# FPGA.net
KiCad netlist of a schematic drawn in Altium Designer
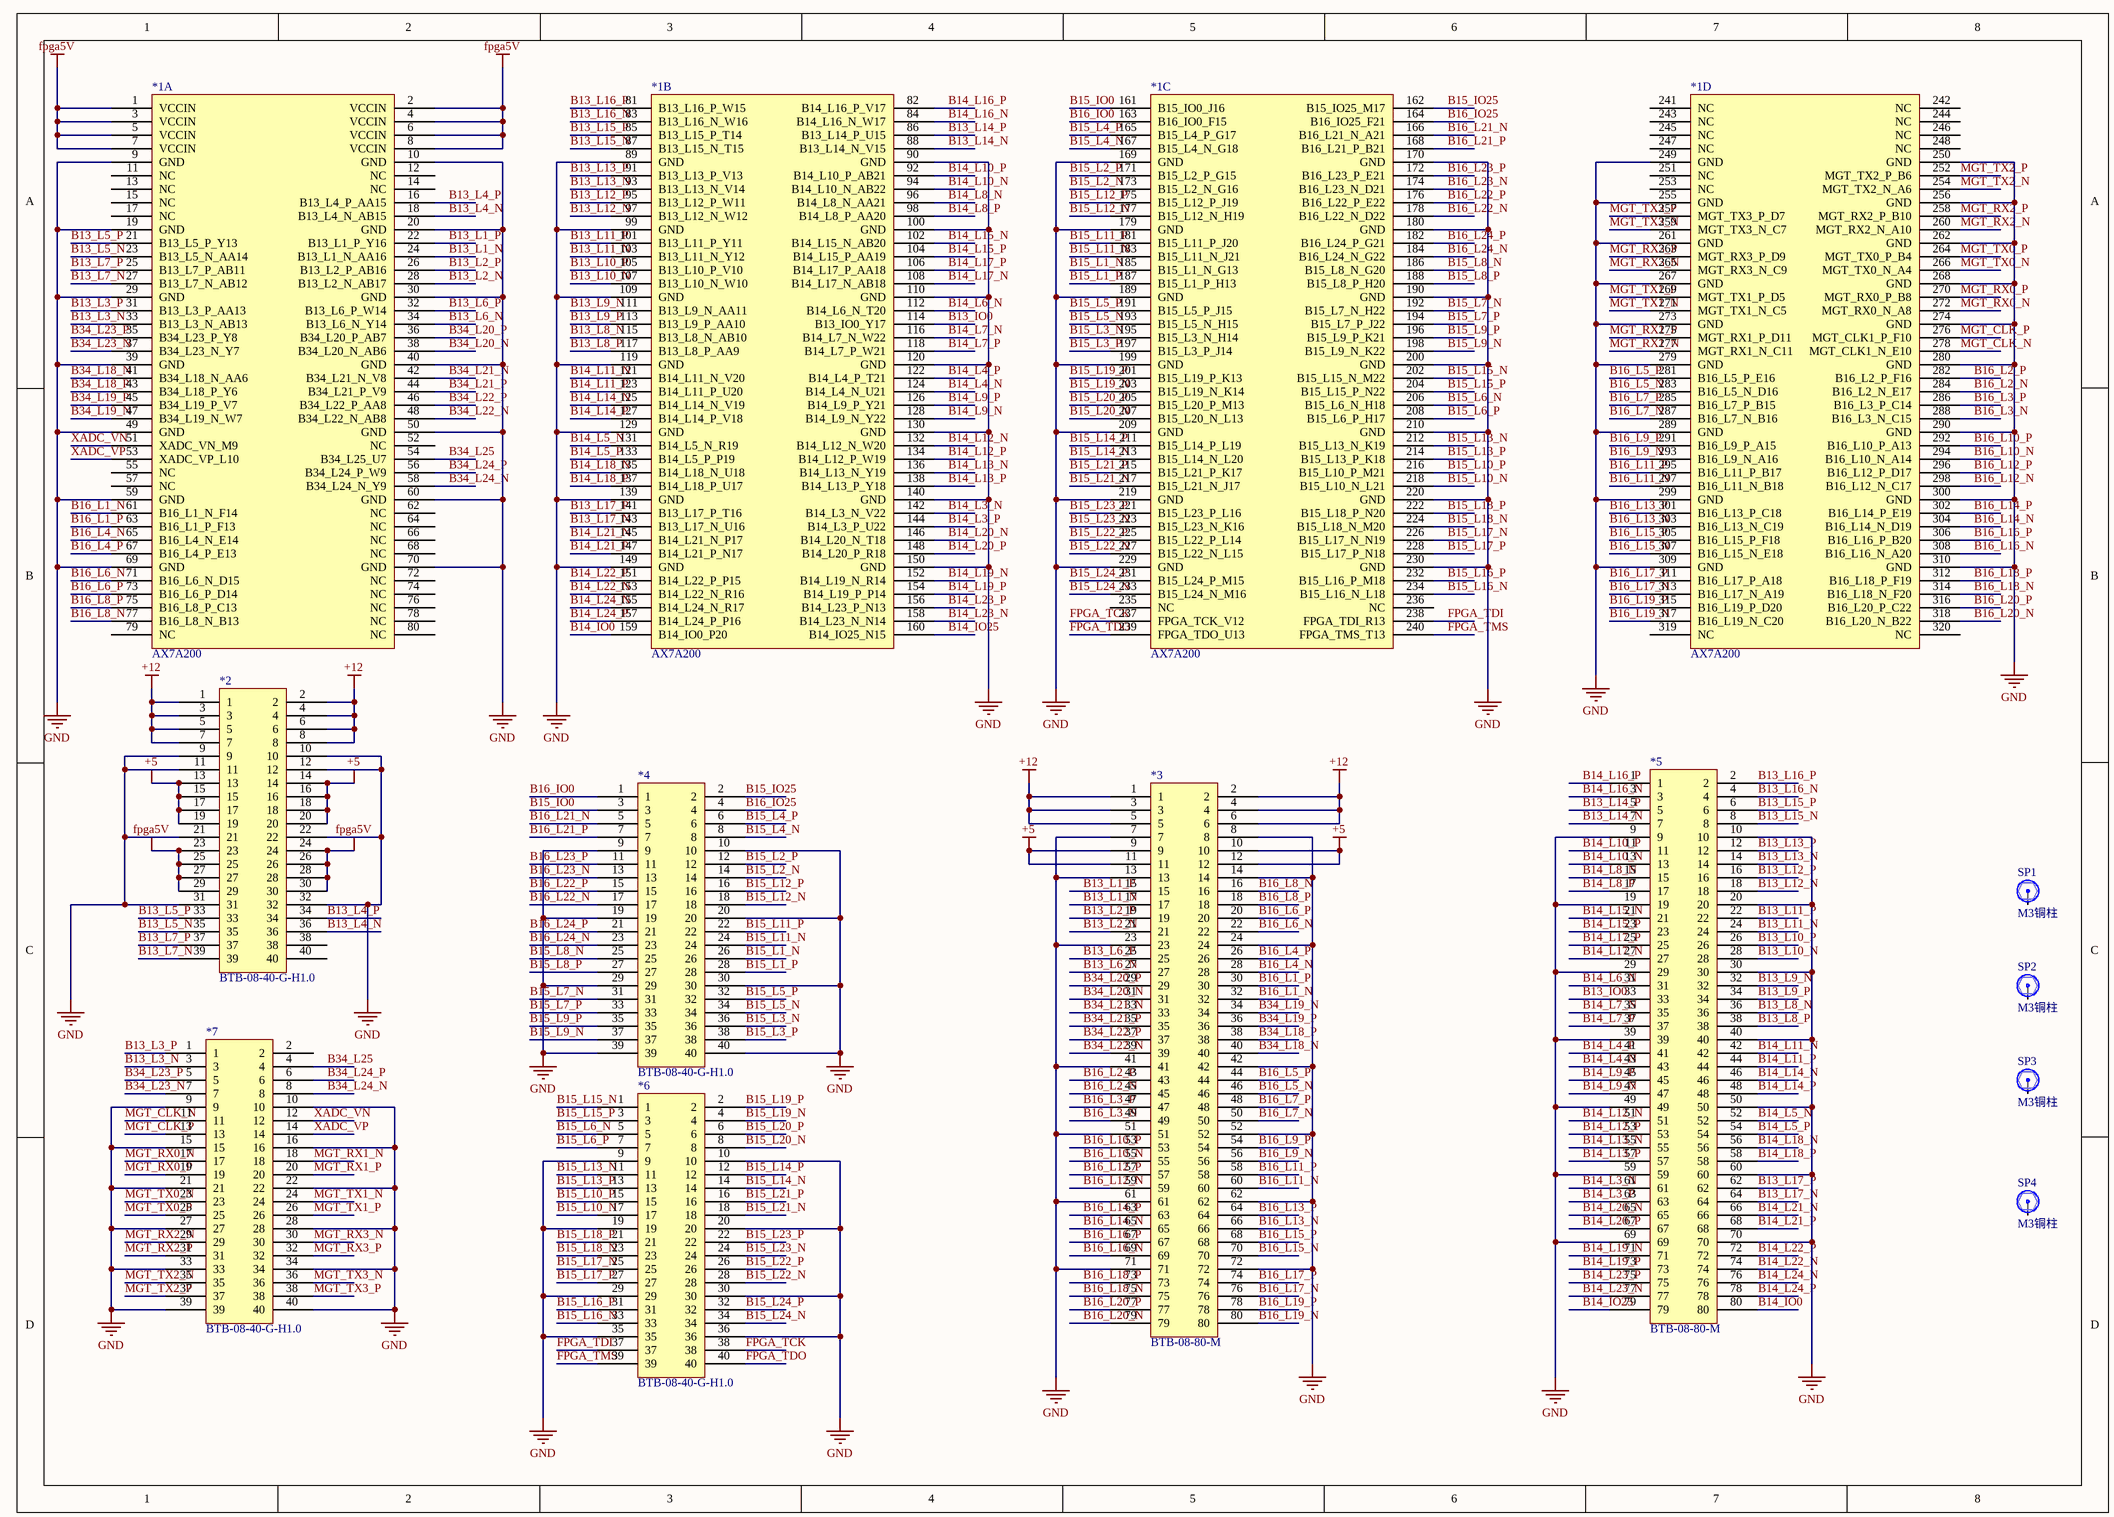
[diagram p0: FPGA.SchDoc]

(export (version "E")
  (design (tool "Eeschema 10.0.6"))
  (components
    (comp (ref "*1") (value "AX7A200") (footprint "AX7A200") (libsource (lib "0.02-模块") (part "AX7A200")))
    (comp (ref "*2")
      (value "BTB-08-40-G-H1.0")
      (footprint "BTB-08-40-G-H1.0")
      (libsource (lib "0.04连接器") (part "BTB-08-40-G-H1.0"))
    )
    (comp (ref "*3")
      (value "BTB-08-80-M")
      (footprint "BTB-08-80-M")
      (libsource (lib "0.04连接器") (part "BTB-08-80-G"))
    )
    (comp (ref "*4")
      (value "BTB-08-40-G-H1.0")
      (footprint "BTB-08-40-G-H1.0")
      (libsource (lib "0.04连接器") (part "BTB-08-40-G-H1.0"))
    )
    (comp (ref "*5")
      (value "BTB-08-80-M")
      (footprint "BTB-08-80-M")
      (libsource (lib "0.04连接器") (part "BTB-08-80-G"))
    )
    (comp (ref "*6")
      (value "BTB-08-40-G-H1.0")
      (footprint "BTB-08-40-G-H1.0")
      (libsource (lib "0.04连接器") (part "BTB-08-40-G-H1.0"))
    )
    (comp (ref "*7")
      (value "BTB-08-40-G-H1.0")
      (footprint "BTB-08-40-G-H1.0")
      (libsource (lib "0.04连接器") (part "BTB-08-40-G-H1.0"))
    )
    (comp (ref "SP1")
      (value "M3铜柱")
      (footprint "M3x10_N")
      (description "铜柱")
      (fields (field (name "版权归属") "封装库来自淘宝 ID：黄晶宝石"))
      (libsource (lib "9.09-固定柱") (part "铜柱大焊盘"))
    )
    (comp (ref "SP2")
      (value "M3铜柱")
      (footprint "M3x10_N")
      (description "铜柱")
      (fields (field (name "版权归属") "封装库来自淘宝 ID：黄晶宝石"))
      (libsource (lib "9.09-固定柱") (part "铜柱大焊盘"))
    )
    (comp (ref "SP3")
      (value "M3铜柱")
      (footprint "M3x10_N")
      (description "铜柱")
      (fields (field (name "版权归属") "封装库来自淘宝 ID：黄晶宝石"))
      (libsource (lib "9.09-固定柱") (part "铜柱大焊盘"))
    )
    (comp (ref "SP4")
      (value "M3铜柱")
      (footprint "M3x10_N")
      (description "铜柱")
      (fields (field (name "版权归属") "封装库来自淘宝 ID：黄晶宝石"))
      (libsource (lib "9.09-固定柱") (part "铜柱大焊盘"))
    )
  )
  (nets
    (net (code "1") (name "+5") (class "Default")
      (node (ref "*2") (pin "13") (pinfunction "13_13") (pintype "passive"))
      (node (ref "*2") (pin "14") (pinfunction "14_14") (pintype "passive"))
      (node (ref "*2") (pin "15") (pinfunction "15_15") (pintype "passive"))
      (node (ref "*2") (pin "16") (pinfunction "16_16") (pintype "passive"))
      (node (ref "*2") (pin "17") (pinfunction "17_17") (pintype "passive"))
      (node (ref "*2") (pin "18") (pinfunction "18_18") (pintype "passive"))
      (node (ref "*2") (pin "19") (pinfunction "19_19") (pintype "passive"))
      (node (ref "*2") (pin "20") (pinfunction "20_20") (pintype "passive"))
      (node (ref "*3") (pin "10") (pinfunction "10_10") (pintype "passive"))
      (node (ref "*3") (pin "11") (pinfunction "11_11") (pintype "passive"))
      (node (ref "*3") (pin "12") (pinfunction "12_12") (pintype "passive"))
      (node (ref "*3") (pin "9") (pinfunction "9_9") (pintype "passive"))
    )
    (net (code "2") (name "+12") (class "Default")
      (node (ref "*2") (pin "1") (pinfunction "1_1") (pintype "passive"))
      (node (ref "*2") (pin "2") (pinfunction "2_2") (pintype "passive"))
      (node (ref "*2") (pin "3") (pinfunction "3_3") (pintype "passive"))
      (node (ref "*2") (pin "4") (pinfunction "4_4") (pintype "passive"))
      (node (ref "*2") (pin "5") (pinfunction "5_5") (pintype "passive"))
      (node (ref "*2") (pin "6") (pinfunction "6_6") (pintype "passive"))
      (node (ref "*2") (pin "7") (pinfunction "7_7") (pintype "passive"))
      (node (ref "*2") (pin "8") (pinfunction "8_8") (pintype "passive"))
      (node (ref "*3") (pin "1") (pinfunction "1_1") (pintype "passive"))
      (node (ref "*3") (pin "2") (pinfunction "2_2") (pintype "passive"))
      (node (ref "*3") (pin "3") (pinfunction "3_3") (pintype "passive"))
      (node (ref "*3") (pin "4") (pinfunction "4_4") (pintype "passive"))
      (node (ref "*3") (pin "5") (pinfunction "5_5") (pintype "passive"))
      (node (ref "*3") (pin "6") (pinfunction "6_6") (pintype "passive"))
    )
    (net (code "3") (name "/B13_IO0") (class "Default")
      (node (ref "*1") (pin "114") (pinfunction "B13_IO0_Y17_114") (pintype "passive"))
      (node (ref "*5") (pin "33") (pinfunction "33_33") (pintype "passive"))
    )
    (net (code "4") (name "/B13_L1_N") (class "Default")
      (node (ref "*1") (pin "24") (pinfunction "B13_L1_N_AA16_24") (pintype "passive"))
      (node (ref "*3") (pin "17") (pinfunction "17_17") (pintype "passive"))
    )
    (net (code "5") (name "/B13_L1_P") (class "Default")
      (node (ref "*1") (pin "22") (pinfunction "B13_L1_P_Y16_22") (pintype "passive"))
      (node (ref "*3") (pin "15") (pinfunction "15_15") (pintype "passive"))
    )
    (net (code "6") (name "/B13_L2_N") (class "Default")
      (node (ref "*1") (pin "28") (pinfunction "B13_L2_N_AB17_28") (pintype "passive"))
      (node (ref "*3") (pin "21") (pinfunction "21_21") (pintype "passive"))
    )
    (net (code "7") (name "/B13_L2_P") (class "Default")
      (node (ref "*1") (pin "26") (pinfunction "B13_L2_P_AB16_26") (pintype "passive"))
      (node (ref "*3") (pin "19") (pinfunction "19_19") (pintype "passive"))
    )
    (net (code "8") (name "/B13_L3_N") (class "Default")
      (node (ref "*1") (pin "33") (pinfunction "B13_L3_N_AB13_33") (pintype "passive"))
      (node (ref "*7") (pin "3") (pinfunction "3_3") (pintype "passive"))
    )
    (net (code "9") (name "/B13_L3_P") (class "Default")
      (node (ref "*1") (pin "31") (pinfunction "B13_L3_P_AA13_31") (pintype "passive"))
      (node (ref "*7") (pin "1") (pinfunction "1_1") (pintype "passive"))
    )
    (net (code "10") (name "/B13_L4_N") (class "Default")
      (node (ref "*1") (pin "18") (pinfunction "B13_L4_N_AB15_18") (pintype "passive"))
      (node (ref "*2") (pin "36") (pinfunction "36_36") (pintype "passive"))
    )
    (net (code "11") (name "/B13_L4_P") (class "Default")
      (node (ref "*1") (pin "16") (pinfunction "B13_L4_P_AA15_16") (pintype "passive"))
      (node (ref "*2") (pin "34") (pinfunction "34_34") (pintype "passive"))
    )
    (net (code "12") (name "/B13_L5_N") (class "Default")
      (node (ref "*1") (pin "23") (pinfunction "B13_L5_N_AA14_23") (pintype "passive"))
      (node (ref "*2") (pin "35") (pinfunction "35_35") (pintype "passive"))
    )
    (net (code "13") (name "/B13_L5_P") (class "Default")
      (node (ref "*1") (pin "21") (pinfunction "B13_L5_P_Y13_21") (pintype "passive"))
      (node (ref "*2") (pin "33") (pinfunction "33_33") (pintype "passive"))
    )
    (net (code "14") (name "/B13_L6_N") (class "Default")
      (node (ref "*1") (pin "34") (pinfunction "B13_L6_N_Y14_34") (pintype "passive"))
      (node (ref "*3") (pin "27") (pinfunction "27_27") (pintype "passive"))
    )
    (net (code "15") (name "/B13_L6_P") (class "Default")
      (node (ref "*1") (pin "32") (pinfunction "B13_L6_P_W14_32") (pintype "passive"))
      (node (ref "*3") (pin "25") (pinfunction "25_25") (pintype "passive"))
    )
    (net (code "16") (name "/B13_L7_N") (class "Default")
      (node (ref "*1") (pin "27") (pinfunction "B13_L7_N_AB12_27") (pintype "passive"))
      (node (ref "*2") (pin "39") (pinfunction "39_39") (pintype "passive"))
    )
    (net (code "17") (name "/B13_L7_P") (class "Default")
      (node (ref "*1") (pin "25") (pinfunction "B13_L7_P_AB11_25") (pintype "passive"))
      (node (ref "*2") (pin "37") (pinfunction "37_37") (pintype "passive"))
    )
    (net (code "18") (name "/B13_L8_N") (class "Default")
      (node (ref "*1") (pin "115") (pinfunction "B13_L8_N_AB10_115") (pintype "passive"))
      (node (ref "*5") (pin "36") (pinfunction "36_36") (pintype "passive"))
    )
    (net (code "19") (name "/B13_L8_P") (class "Default")
      (node (ref "*1") (pin "117") (pinfunction "B13_L8_P_AA9_117") (pintype "passive"))
      (node (ref "*5") (pin "38") (pinfunction "38_38") (pintype "passive"))
    )
    (net (code "20") (name "/B13_L9_N") (class "Default")
      (node (ref "*1") (pin "111") (pinfunction "B13_L9_N_AA11_111") (pintype "passive"))
      (node (ref "*5") (pin "32") (pinfunction "32_32") (pintype "passive"))
    )
    (net (code "21") (name "/B13_L9_P") (class "Default")
      (node (ref "*1") (pin "113") (pinfunction "B13_L9_P_AA10_113") (pintype "passive"))
      (node (ref "*5") (pin "34") (pinfunction "34_34") (pintype "passive"))
    )
    (net (code "22") (name "/B13_L10_N") (class "Default")
      (node (ref "*1") (pin "107") (pinfunction "B13_L10_N_W10_107") (pintype "passive"))
      (node (ref "*5") (pin "28") (pinfunction "28_28") (pintype "passive"))
    )
    (net (code "23") (name "/B13_L10_P") (class "Default")
      (node (ref "*1") (pin "105") (pinfunction "B13_L10_P_V10_105") (pintype "passive"))
      (node (ref "*5") (pin "26") (pinfunction "26_26") (pintype "passive"))
    )
    (net (code "24") (name "/B13_L11_N") (class "Default")
      (node (ref "*1") (pin "103") (pinfunction "B13_L11_N_Y12_103") (pintype "passive"))
      (node (ref "*5") (pin "24") (pinfunction "24_24") (pintype "passive"))
    )
    (net (code "25") (name "/B13_L11_P") (class "Default")
      (node (ref "*1") (pin "101") (pinfunction "B13_L11_P_Y11_101") (pintype "passive"))
      (node (ref "*5") (pin "22") (pinfunction "22_22") (pintype "passive"))
    )
    (net (code "26") (name "/B13_L12_N") (class "Default")
      (node (ref "*1") (pin "97") (pinfunction "B13_L12_N_W12_97") (pintype "passive"))
      (node (ref "*5") (pin "18") (pinfunction "18_18") (pintype "passive"))
    )
    (net (code "27") (name "/B13_L12_P") (class "Default")
      (node (ref "*1") (pin "95") (pinfunction "B13_L12_P_W11_95") (pintype "passive"))
      (node (ref "*5") (pin "16") (pinfunction "16_16") (pintype "passive"))
    )
    (net (code "28") (name "/B13_L13_N") (class "Default")
      (node (ref "*1") (pin "93") (pinfunction "B13_L13_N_V14_93") (pintype "passive"))
      (node (ref "*5") (pin "14") (pinfunction "14_14") (pintype "passive"))
    )
    (net (code "29") (name "/B13_L13_P") (class "Default")
      (node (ref "*1") (pin "91") (pinfunction "B13_L13_P_V13_91") (pintype "passive"))
      (node (ref "*5") (pin "12") (pinfunction "12_12") (pintype "passive"))
    )
    (net (code "30") (name "/B13_L14_N") (class "Default")
      (node (ref "*1") (pin "88") (pinfunction "B13_L14_N_V15_88") (pintype "passive"))
      (node (ref "*5") (pin "7") (pinfunction "7_7") (pintype "passive"))
    )
    (net (code "31") (name "/B13_L14_P") (class "Default")
      (node (ref "*1") (pin "86") (pinfunction "B13_L14_P_U15_86") (pintype "passive"))
      (node (ref "*5") (pin "5") (pinfunction "5_5") (pintype "passive"))
    )
    (net (code "32") (name "/B13_L15_N") (class "Default")
      (node (ref "*1") (pin "87") (pinfunction "B13_L15_N_T15_87") (pintype "passive"))
      (node (ref "*5") (pin "8") (pinfunction "8_8") (pintype "passive"))
    )
    (net (code "33") (name "/B13_L15_P") (class "Default")
      (node (ref "*1") (pin "85") (pinfunction "B13_L15_P_T14_85") (pintype "passive"))
      (node (ref "*5") (pin "6") (pinfunction "6_6") (pintype "passive"))
    )
    (net (code "34") (name "/B13_L16_N") (class "Default")
      (node (ref "*1") (pin "83") (pinfunction "B13_L16_N_W16_83") (pintype "passive"))
      (node (ref "*5") (pin "4") (pinfunction "4_4") (pintype "passive"))
    )
    (net (code "35") (name "/B13_L16_P") (class "Default")
      (node (ref "*1") (pin "81") (pinfunction "B13_L16_P_W15_81") (pintype "passive"))
      (node (ref "*5") (pin "2") (pinfunction "2_2") (pintype "passive"))
    )
    (net (code "36") (name "/B13_L17_N") (class "Default")
      (node (ref "*1") (pin "143") (pinfunction "B13_L17_N_U16_143") (pintype "passive"))
      (node (ref "*5") (pin "64") (pinfunction "64_64") (pintype "passive"))
    )
    (net (code "37") (name "/B13_L17_P") (class "Default")
      (node (ref "*1") (pin "141") (pinfunction "B13_L17_P_T16_141") (pintype "passive"))
      (node (ref "*5") (pin "62") (pinfunction "62_62") (pintype "passive"))
    )
    (net (code "38") (name "/B14_IO0") (class "Default")
      (node (ref "*1") (pin "159") (pinfunction "B14_IO0_P20_159") (pintype "passive"))
      (node (ref "*5") (pin "80") (pinfunction "80_80") (pintype "passive"))
    )
    (net (code "39") (name "/B14_IO25") (class "Default")
      (node (ref "*1") (pin "160") (pinfunction "B14_IO25_N15_160") (pintype "passive"))
      (node (ref "*5") (pin "79") (pinfunction "79_79") (pintype "passive"))
    )
    (net (code "40") (name "/B14_L3_N") (class "Default")
      (node (ref "*1") (pin "142") (pinfunction "B14_L3_N_V22_142") (pintype "passive"))
      (node (ref "*5") (pin "61") (pinfunction "61_61") (pintype "passive"))
    )
    (net (code "41") (name "/B14_L3_P") (class "Default")
      (node (ref "*1") (pin "144") (pinfunction "B14_L3_P_U22_144") (pintype "passive"))
      (node (ref "*5") (pin "63") (pinfunction "63_63") (pintype "passive"))
    )
    (net (code "42") (name "/B14_L4_N") (class "Default")
      (node (ref "*1") (pin "124") (pinfunction "B14_L4_N_U21_124") (pintype "passive"))
      (node (ref "*5") (pin "43") (pinfunction "43_43") (pintype "passive"))
    )
    (net (code "43") (name "/B14_L4_P") (class "Default")
      (node (ref "*1") (pin "122") (pinfunction "B14_L4_P_T21_122") (pintype "passive"))
      (node (ref "*5") (pin "41") (pinfunction "41_41") (pintype "passive"))
    )
    (net (code "44") (name "/B14_L5_N") (class "Default")
      (node (ref "*1") (pin "131") (pinfunction "B14_L5_N_R19_131") (pintype "passive"))
      (node (ref "*5") (pin "52") (pinfunction "52_52") (pintype "passive"))
    )
    (net (code "45") (name "/B14_L5_P") (class "Default")
      (node (ref "*1") (pin "133") (pinfunction "B14_L5_P_P19_133") (pintype "passive"))
      (node (ref "*5") (pin "54") (pinfunction "54_54") (pintype "passive"))
    )
    (net (code "46") (name "/B14_L6_N") (class "Default")
      (node (ref "*1") (pin "112") (pinfunction "B14_L6_N_T20_112") (pintype "passive"))
      (node (ref "*5") (pin "31") (pinfunction "31_31") (pintype "passive"))
    )
    (net (code "47") (name "/B14_L7_N") (class "Default")
      (node (ref "*1") (pin "116") (pinfunction "B14_L7_N_W22_116") (pintype "passive"))
      (node (ref "*5") (pin "35") (pinfunction "35_35") (pintype "passive"))
    )
    (net (code "48") (name "/B14_L7_P") (class "Default")
      (node (ref "*1") (pin "118") (pinfunction "B14_L7_P_W21_118") (pintype "passive"))
      (node (ref "*5") (pin "37") (pinfunction "37_37") (pintype "passive"))
    )
    (net (code "49") (name "/B14_L8_N") (class "Default")
      (node (ref "*1") (pin "96") (pinfunction "B14_L8_N_AA21_96") (pintype "passive"))
      (node (ref "*5") (pin "15") (pinfunction "15_15") (pintype "passive"))
    )
    (net (code "50") (name "/B14_L8_P") (class "Default")
      (node (ref "*1") (pin "98") (pinfunction "B14_L8_P_AA20_98") (pintype "passive"))
      (node (ref "*5") (pin "17") (pinfunction "17_17") (pintype "passive"))
    )
    (net (code "51") (name "/B14_L9_N") (class "Default")
      (node (ref "*1") (pin "128") (pinfunction "B14_L9_N_Y22_128") (pintype "passive"))
      (node (ref "*5") (pin "47") (pinfunction "47_47") (pintype "passive"))
    )
    (net (code "52") (name "/B14_L9_P") (class "Default")
      (node (ref "*1") (pin "126") (pinfunction "B14_L9_P_Y21_126") (pintype "passive"))
      (node (ref "*5") (pin "45") (pinfunction "45_45") (pintype "passive"))
    )
    (net (code "53") (name "/B14_L10_N") (class "Default")
      (node (ref "*1") (pin "94") (pinfunction "B14_L10_N_AB22_94") (pintype "passive"))
      (node (ref "*5") (pin "13") (pinfunction "13_13") (pintype "passive"))
    )
    (net (code "54") (name "/B14_L10_P") (class "Default")
      (node (ref "*1") (pin "92") (pinfunction "B14_L10_P_AB21_92") (pintype "passive"))
      (node (ref "*5") (pin "11") (pinfunction "11_11") (pintype "passive"))
    )
    (net (code "55") (name "/B14_L11_N") (class "Default")
      (node (ref "*1") (pin "121") (pinfunction "B14_L11_N_V20_121") (pintype "passive"))
      (node (ref "*5") (pin "42") (pinfunction "42_42") (pintype "passive"))
    )
    (net (code "56") (name "/B14_L11_P") (class "Default")
      (node (ref "*1") (pin "123") (pinfunction "B14_L11_P_U20_123") (pintype "passive"))
      (node (ref "*5") (pin "44") (pinfunction "44_44") (pintype "passive"))
    )
    (net (code "57") (name "/B14_L12_N") (class "Default")
      (node (ref "*1") (pin "132") (pinfunction "B14_L12_N_W20_132") (pintype "passive"))
      (node (ref "*5") (pin "51") (pinfunction "51_51") (pintype "passive"))
    )
    (net (code "58") (name "/B14_L12_P") (class "Default")
      (node (ref "*1") (pin "134") (pinfunction "B14_L12_P_W19_134") (pintype "passive"))
      (node (ref "*5") (pin "53") (pinfunction "53_53") (pintype "passive"))
    )
    (net (code "59") (name "/B14_L13_N") (class "Default")
      (node (ref "*1") (pin "136") (pinfunction "B14_L13_N_Y19_136") (pintype "passive"))
      (node (ref "*5") (pin "55") (pinfunction "55_55") (pintype "passive"))
    )
    (net (code "60") (name "/B14_L13_P") (class "Default")
      (node (ref "*1") (pin "138") (pinfunction "B14_L13_P_Y18_138") (pintype "passive"))
      (node (ref "*5") (pin "57") (pinfunction "57_57") (pintype "passive"))
    )
    (net (code "61") (name "/B14_L14_N") (class "Default")
      (node (ref "*1") (pin "125") (pinfunction "B14_L14_N_V19_125") (pintype "passive"))
      (node (ref "*5") (pin "46") (pinfunction "46_46") (pintype "passive"))
    )
    (net (code "62") (name "/B14_L14_P") (class "Default")
      (node (ref "*1") (pin "127") (pinfunction "B14_L14_P_V18_127") (pintype "passive"))
      (node (ref "*5") (pin "48") (pinfunction "48_48") (pintype "passive"))
    )
    (net (code "63") (name "/B14_L15_N") (class "Default")
      (node (ref "*1") (pin "102") (pinfunction "B14_L15_N_AB20_102") (pintype "passive"))
      (node (ref "*5") (pin "21") (pinfunction "21_21") (pintype "passive"))
    )
    (net (code "64") (name "/B14_L15_P") (class "Default")
      (node (ref "*1") (pin "104") (pinfunction "B14_L15_P_AA19_104") (pintype "passive"))
      (node (ref "*5") (pin "23") (pinfunction "23_23") (pintype "passive"))
    )
    (net (code "65") (name "/B14_L16_N") (class "Default")
      (node (ref "*1") (pin "84") (pinfunction "B14_L16_N_W17_84") (pintype "passive"))
      (node (ref "*5") (pin "3") (pinfunction "3_3") (pintype "passive"))
    )
    (net (code "66") (name "/B14_L16_P") (class "Default")
      (node (ref "*1") (pin "82") (pinfunction "B14_L16_P_V17_82") (pintype "passive"))
      (node (ref "*5") (pin "1") (pinfunction "1_1") (pintype "passive"))
    )
    (net (code "67") (name "/B14_L17_N") (class "Default")
      (node (ref "*1") (pin "108") (pinfunction "B14_L17_N_AB18_108") (pintype "passive"))
      (node (ref "*5") (pin "27") (pinfunction "27_27") (pintype "passive"))
    )
    (net (code "68") (name "/B14_L17_P") (class "Default")
      (node (ref "*1") (pin "106") (pinfunction "B14_L17_P_AA18_106") (pintype "passive"))
      (node (ref "*5") (pin "25") (pinfunction "25_25") (pintype "passive"))
    )
    (net (code "69") (name "/B14_L18_N") (class "Default")
      (node (ref "*1") (pin "135") (pinfunction "B14_L18_N_U18_135") (pintype "passive"))
      (node (ref "*5") (pin "56") (pinfunction "56_56") (pintype "passive"))
    )
    (net (code "70") (name "/B14_L18_P") (class "Default")
      (node (ref "*1") (pin "137") (pinfunction "B14_L18_P_U17_137") (pintype "passive"))
      (node (ref "*5") (pin "58") (pinfunction "58_58") (pintype "passive"))
    )
    (net (code "71") (name "/B14_L19_N") (class "Default")
      (node (ref "*1") (pin "152") (pinfunction "B14_L19_N_R14_152") (pintype "passive"))
      (node (ref "*5") (pin "71") (pinfunction "71_71") (pintype "passive"))
    )
    (net (code "72") (name "/B14_L19_P") (class "Default")
      (node (ref "*1") (pin "154") (pinfunction "B14_L19_P_P14_154") (pintype "passive"))
      (node (ref "*5") (pin "73") (pinfunction "73_73") (pintype "passive"))
    )
    (net (code "73") (name "/B14_L20_N") (class "Default")
      (node (ref "*1") (pin "146") (pinfunction "B14_L20_N_T18_146") (pintype "passive"))
      (node (ref "*5") (pin "65") (pinfunction "65_65") (pintype "passive"))
    )
    (net (code "74") (name "/B14_L20_P") (class "Default")
      (node (ref "*1") (pin "148") (pinfunction "B14_L20_P_R18_148") (pintype "passive"))
      (node (ref "*5") (pin "67") (pinfunction "67_67") (pintype "passive"))
    )
    (net (code "75") (name "/B14_L21_N") (class "Default")
      (node (ref "*1") (pin "145") (pinfunction "B14_L21_N_P17_145") (pintype "passive"))
      (node (ref "*5") (pin "66") (pinfunction "66_66") (pintype "passive"))
    )
    (net (code "76") (name "/B14_L21_P") (class "Default")
      (node (ref "*1") (pin "147") (pinfunction "B14_L21_P_N17_147") (pintype "passive"))
      (node (ref "*5") (pin "68") (pinfunction "68_68") (pintype "passive"))
    )
    (net (code "77") (name "/B14_L22_N") (class "Default")
      (node (ref "*1") (pin "153") (pinfunction "B14_L22_N_R16_153") (pintype "passive"))
      (node (ref "*5") (pin "74") (pinfunction "74_74") (pintype "passive"))
    )
    (net (code "78") (name "/B14_L22_P") (class "Default")
      (node (ref "*1") (pin "151") (pinfunction "B14_L22_P_P15_151") (pintype "passive"))
      (node (ref "*5") (pin "72") (pinfunction "72_72") (pintype "passive"))
    )
    (net (code "79") (name "/B14_L23_N") (class "Default")
      (node (ref "*1") (pin "158") (pinfunction "B14_L23_N_N14_158") (pintype "passive"))
      (node (ref "*5") (pin "77") (pinfunction "77_77") (pintype "passive"))
    )
    (net (code "80") (name "/B14_L23_P") (class "Default")
      (node (ref "*1") (pin "156") (pinfunction "B14_L23_P_N13_156") (pintype "passive"))
      (node (ref "*5") (pin "75") (pinfunction "75_75") (pintype "passive"))
    )
    (net (code "81") (name "/B14_L24_N") (class "Default")
      (node (ref "*1") (pin "155") (pinfunction "B14_L24_N_R17_155") (pintype "passive"))
      (node (ref "*5") (pin "76") (pinfunction "76_76") (pintype "passive"))
    )
    (net (code "82") (name "/B14_L24_P") (class "Default")
      (node (ref "*1") (pin "157") (pinfunction "B14_L24_P_P16_157") (pintype "passive"))
      (node (ref "*5") (pin "78") (pinfunction "78_78") (pintype "passive"))
    )
    (net (code "83") (name "/B15_IO0") (class "Default")
      (node (ref "*1") (pin "161") (pinfunction "B15_IO0_J16_161") (pintype "passive"))
      (node (ref "*4") (pin "3") (pinfunction "3_3") (pintype "passive"))
    )
    (net (code "84") (name "/B15_IO25") (class "Default")
      (node (ref "*1") (pin "162") (pinfunction "B15_IO25_M17_162") (pintype "passive"))
      (node (ref "*4") (pin "2") (pinfunction "2_2") (pintype "passive"))
    )
    (net (code "85") (name "/B15_L1_N") (class "Default")
      (node (ref "*1") (pin "185") (pinfunction "B15_L1_N_G13_185") (pintype "passive"))
      (node (ref "*4") (pin "26") (pinfunction "26_26") (pintype "passive"))
    )
    (net (code "86") (name "/B15_L1_P") (class "Default")
      (node (ref "*1") (pin "187") (pinfunction "B15_L1_P_H13_187") (pintype "passive"))
      (node (ref "*4") (pin "28") (pinfunction "28_28") (pintype "passive"))
    )
    (net (code "87") (name "/B15_L2_N") (class "Default")
      (node (ref "*1") (pin "173") (pinfunction "B15_L2_N_G16_173") (pintype "passive"))
      (node (ref "*4") (pin "14") (pinfunction "14_14") (pintype "passive"))
    )
    (net (code "88") (name "/B15_L2_P") (class "Default")
      (node (ref "*1") (pin "171") (pinfunction "B15_L2_P_G15_171") (pintype "passive"))
      (node (ref "*4") (pin "12") (pinfunction "12_12") (pintype "passive"))
    )
    (net (code "89") (name "/B15_L3_N") (class "Default")
      (node (ref "*1") (pin "195") (pinfunction "B15_L3_N_H14_195") (pintype "passive"))
      (node (ref "*4") (pin "36") (pinfunction "36_36") (pintype "passive"))
    )
    (net (code "90") (name "/B15_L3_P") (class "Default")
      (node (ref "*1") (pin "197") (pinfunction "B15_L3_P_J14_197") (pintype "passive"))
      (node (ref "*4") (pin "38") (pinfunction "38_38") (pintype "passive"))
    )
    (net (code "91") (name "/B15_L4_N") (class "Default")
      (node (ref "*1") (pin "167") (pinfunction "B15_L4_N_G18_167") (pintype "passive"))
      (node (ref "*4") (pin "8") (pinfunction "8_8") (pintype "passive"))
    )
    (net (code "92") (name "/B15_L4_P") (class "Default")
      (node (ref "*1") (pin "165") (pinfunction "B15_L4_P_G17_165") (pintype "passive"))
      (node (ref "*4") (pin "6") (pinfunction "6_6") (pintype "passive"))
    )
    (net (code "93") (name "/B15_L5_N") (class "Default")
      (node (ref "*1") (pin "193") (pinfunction "B15_L5_N_H15_193") (pintype "passive"))
      (node (ref "*4") (pin "34") (pinfunction "34_34") (pintype "passive"))
    )
    (net (code "94") (name "/B15_L5_P") (class "Default")
      (node (ref "*1") (pin "191") (pinfunction "B15_L5_P_J15_191") (pintype "passive"))
      (node (ref "*4") (pin "32") (pinfunction "32_32") (pintype "passive"))
    )
    (net (code "95") (name "/B15_L6_N") (class "Default")
      (node (ref "*1") (pin "206") (pinfunction "B15_L6_N_H18_206") (pintype "passive"))
      (node (ref "*6") (pin "5") (pinfunction "5_5") (pintype "passive"))
    )
    (net (code "96") (name "/B15_L6_P") (class "Default")
      (node (ref "*1") (pin "208") (pinfunction "B15_L6_P_H17_208") (pintype "passive"))
      (node (ref "*6") (pin "7") (pinfunction "7_7") (pintype "passive"))
    )
    (net (code "97") (name "/B15_L7_N") (class "Default")
      (node (ref "*1") (pin "192") (pinfunction "B15_L7_N_H22_192") (pintype "passive"))
      (node (ref "*4") (pin "31") (pinfunction "31_31") (pintype "passive"))
    )
    (net (code "98") (name "/B15_L7_P") (class "Default")
      (node (ref "*1") (pin "194") (pinfunction "B15_L7_P_J22_194") (pintype "passive"))
      (node (ref "*4") (pin "33") (pinfunction "33_33") (pintype "passive"))
    )
    (net (code "99") (name "/B15_L8_N") (class "Default")
      (node (ref "*1") (pin "186") (pinfunction "B15_L8_N_G20_186") (pintype "passive"))
      (node (ref "*4") (pin "25") (pinfunction "25_25") (pintype "passive"))
    )
    (net (code "100") (name "/B15_L8_P") (class "Default")
      (node (ref "*1") (pin "188") (pinfunction "B15_L8_P_H20_188") (pintype "passive"))
      (node (ref "*4") (pin "27") (pinfunction "27_27") (pintype "passive"))
    )
    (net (code "101") (name "/B15_L9_N") (class "Default")
      (node (ref "*1") (pin "198") (pinfunction "B15_L9_N_K22_198") (pintype "passive"))
      (node (ref "*4") (pin "37") (pinfunction "37_37") (pintype "passive"))
    )
    (net (code "102") (name "/B15_L9_P") (class "Default")
      (node (ref "*1") (pin "196") (pinfunction "B15_L9_P_K21_196") (pintype "passive"))
      (node (ref "*4") (pin "35") (pinfunction "35_35") (pintype "passive"))
    )
    (net (code "103") (name "/B15_L10_N") (class "Default")
      (node (ref "*1") (pin "218") (pinfunction "B15_L10_N_L21_218") (pintype "passive"))
      (node (ref "*6") (pin "17") (pinfunction "17_17") (pintype "passive"))
    )
    (net (code "104") (name "/B15_L10_P") (class "Default")
      (node (ref "*1") (pin "216") (pinfunction "B15_L10_P_M21_216") (pintype "passive"))
      (node (ref "*6") (pin "15") (pinfunction "15_15") (pintype "passive"))
    )
    (net (code "105") (name "/B15_L11_N") (class "Default")
      (node (ref "*1") (pin "183") (pinfunction "B15_L11_N_J21_183") (pintype "passive"))
      (node (ref "*4") (pin "24") (pinfunction "24_24") (pintype "passive"))
    )
    (net (code "106") (name "/B15_L11_P") (class "Default")
      (node (ref "*1") (pin "181") (pinfunction "B15_L11_P_J20_181") (pintype "passive"))
      (node (ref "*4") (pin "22") (pinfunction "22_22") (pintype "passive"))
    )
    (net (code "107") (name "/B15_L12_N") (class "Default")
      (node (ref "*1") (pin "177") (pinfunction "B15_L12_N_H19_177") (pintype "passive"))
      (node (ref "*4") (pin "18") (pinfunction "18_18") (pintype "passive"))
    )
    (net (code "108") (name "/B15_L12_P") (class "Default")
      (node (ref "*1") (pin "175") (pinfunction "B15_L12_P_J19_175") (pintype "passive"))
      (node (ref "*4") (pin "16") (pinfunction "16_16") (pintype "passive"))
    )
    (net (code "109") (name "/B15_L13_N") (class "Default")
      (node (ref "*1") (pin "212") (pinfunction "B15_L13_N_K19_212") (pintype "passive"))
      (node (ref "*6") (pin "11") (pinfunction "11_11") (pintype "passive"))
    )
    (net (code "110") (name "/B15_L13_P") (class "Default")
      (node (ref "*1") (pin "214") (pinfunction "B15_L13_P_K18_214") (pintype "passive"))
      (node (ref "*6") (pin "13") (pinfunction "13_13") (pintype "passive"))
    )
    (net (code "111") (name "/B15_L14_N") (class "Default")
      (node (ref "*1") (pin "213") (pinfunction "B15_L14_N_L20_213") (pintype "passive"))
      (node (ref "*6") (pin "14") (pinfunction "14_14") (pintype "passive"))
    )
    (net (code "112") (name "/B15_L14_P") (class "Default")
      (node (ref "*1") (pin "211") (pinfunction "B15_L14_P_L19_211") (pintype "passive"))
      (node (ref "*6") (pin "12") (pinfunction "12_12") (pintype "passive"))
    )
    (net (code "113") (name "/B15_L15_N") (class "Default")
      (node (ref "*1") (pin "202") (pinfunction "B15_L15_N_M22_202") (pintype "passive"))
      (node (ref "*6") (pin "1") (pinfunction "1_1") (pintype "passive"))
    )
    (net (code "114") (name "/B15_L15_P") (class "Default")
      (node (ref "*1") (pin "204") (pinfunction "B15_L15_P_N22_204") (pintype "passive"))
      (node (ref "*6") (pin "3") (pinfunction "3_3") (pintype "passive"))
    )
    (net (code "115") (name "/B15_L16_N") (class "Default")
      (node (ref "*1") (pin "234") (pinfunction "B15_L16_N_L18_234") (pintype "passive"))
      (node (ref "*6") (pin "33") (pinfunction "33_33") (pintype "passive"))
    )
    (net (code "116") (name "/B15_L16_P") (class "Default")
      (node (ref "*1") (pin "232") (pinfunction "B15_L16_P_M18_232") (pintype "passive"))
      (node (ref "*6") (pin "31") (pinfunction "31_31") (pintype "passive"))
    )
    (net (code "117") (name "/B15_L17_N") (class "Default")
      (node (ref "*1") (pin "226") (pinfunction "B15_L17_N_N19_226") (pintype "passive"))
      (node (ref "*6") (pin "25") (pinfunction "25_25") (pintype "passive"))
    )
    (net (code "118") (name "/B15_L17_P") (class "Default")
      (node (ref "*1") (pin "228") (pinfunction "B15_L17_P_N18_228") (pintype "passive"))
      (node (ref "*6") (pin "27") (pinfunction "27_27") (pintype "passive"))
    )
    (net (code "119") (name "/B15_L18_N") (class "Default")
      (node (ref "*1") (pin "224") (pinfunction "B15_L18_N_M20_224") (pintype "passive"))
      (node (ref "*6") (pin "23") (pinfunction "23_23") (pintype "passive"))
    )
    (net (code "120") (name "/B15_L18_P") (class "Default")
      (node (ref "*1") (pin "222") (pinfunction "B15_L18_P_N20_222") (pintype "passive"))
      (node (ref "*6") (pin "21") (pinfunction "21_21") (pintype "passive"))
    )
    (net (code "121") (name "/B15_L19_N") (class "Default")
      (node (ref "*1") (pin "203") (pinfunction "B15_L19_N_K14_203") (pintype "passive"))
      (node (ref "*6") (pin "4") (pinfunction "4_4") (pintype "passive"))
    )
    (net (code "122") (name "/B15_L19_P") (class "Default")
      (node (ref "*1") (pin "201") (pinfunction "B15_L19_P_K13_201") (pintype "passive"))
      (node (ref "*6") (pin "2") (pinfunction "2_2") (pintype "passive"))
    )
    (net (code "123") (name "/B15_L20_N") (class "Default")
      (node (ref "*1") (pin "207") (pinfunction "B15_L20_N_L13_207") (pintype "passive"))
      (node (ref "*6") (pin "8") (pinfunction "8_8") (pintype "passive"))
    )
    (net (code "124") (name "/B15_L20_P") (class "Default")
      (node (ref "*1") (pin "205") (pinfunction "B15_L20_P_M13_205") (pintype "passive"))
      (node (ref "*6") (pin "6") (pinfunction "6_6") (pintype "passive"))
    )
    (net (code "125") (name "/B15_L21_N") (class "Default")
      (node (ref "*1") (pin "217") (pinfunction "B15_L21_N_J17_217") (pintype "passive"))
      (node (ref "*6") (pin "18") (pinfunction "18_18") (pintype "passive"))
    )
    (net (code "126") (name "/B15_L21_P") (class "Default")
      (node (ref "*1") (pin "215") (pinfunction "B15_L21_P_K17_215") (pintype "passive"))
      (node (ref "*6") (pin "16") (pinfunction "16_16") (pintype "passive"))
    )
    (net (code "127") (name "/B15_L22_N") (class "Default")
      (node (ref "*1") (pin "227") (pinfunction "B15_L22_N_L15_227") (pintype "passive"))
      (node (ref "*6") (pin "28") (pinfunction "28_28") (pintype "passive"))
    )
    (net (code "128") (name "/B15_L22_P") (class "Default")
      (node (ref "*1") (pin "225") (pinfunction "B15_L22_P_L14_225") (pintype "passive"))
      (node (ref "*6") (pin "26") (pinfunction "26_26") (pintype "passive"))
    )
    (net (code "129") (name "/B15_L23_N") (class "Default")
      (node (ref "*1") (pin "223") (pinfunction "B15_L23_N_K16_223") (pintype "passive"))
      (node (ref "*6") (pin "24") (pinfunction "24_24") (pintype "passive"))
    )
    (net (code "130") (name "/B15_L23_P") (class "Default")
      (node (ref "*1") (pin "221") (pinfunction "B15_L23_P_L16_221") (pintype "passive"))
      (node (ref "*6") (pin "22") (pinfunction "22_22") (pintype "passive"))
    )
    (net (code "131") (name "/B15_L24_N") (class "Default")
      (node (ref "*1") (pin "233") (pinfunction "B15_L24_N_M16_233") (pintype "passive"))
      (node (ref "*6") (pin "34") (pinfunction "34_34") (pintype "passive"))
    )
    (net (code "132") (name "/B15_L24_P") (class "Default")
      (node (ref "*1") (pin "231") (pinfunction "B15_L24_P_M15_231") (pintype "passive"))
      (node (ref "*6") (pin "32") (pinfunction "32_32") (pintype "passive"))
    )
    (net (code "133") (name "/B16_IO0") (class "Default")
      (node (ref "*1") (pin "163") (pinfunction "B16_IO0_F15_163") (pintype "passive"))
      (node (ref "*4") (pin "1") (pinfunction "1_1") (pintype "passive"))
    )
    (net (code "134") (name "/B16_IO25") (class "Default")
      (node (ref "*1") (pin "164") (pinfunction "B16_IO25_F21_164") (pintype "passive"))
      (node (ref "*4") (pin "4") (pinfunction "4_4") (pintype "passive"))
    )
    (net (code "135") (name "/B16_L1_N") (class "Default")
      (node (ref "*1") (pin "61") (pinfunction "B16_L1_N_F14_61") (pintype "passive"))
      (node (ref "*3") (pin "32") (pinfunction "32_32") (pintype "passive"))
    )
    (net (code "136") (name "/B16_L1_P") (class "Default")
      (node (ref "*1") (pin "63") (pinfunction "B16_L1_P_F13_63") (pintype "passive"))
      (node (ref "*3") (pin "30") (pinfunction "30_30") (pintype "passive"))
    )
    (net (code "137") (name "/B16_L2_N") (class "Default")
      (node (ref "*1") (pin "284") (pinfunction "B16_L2_N_E17_284") (pintype "passive"))
      (node (ref "*3") (pin "45") (pinfunction "45_45") (pintype "passive"))
    )
    (net (code "138") (name "/B16_L2_P") (class "Default")
      (node (ref "*1") (pin "282") (pinfunction "B16_L2_P_F16_282") (pintype "passive"))
      (node (ref "*3") (pin "43") (pinfunction "43_43") (pintype "passive"))
    )
    (net (code "139") (name "/B16_L3_N") (class "Default")
      (node (ref "*1") (pin "288") (pinfunction "B16_L3_N_C15_288") (pintype "passive"))
      (node (ref "*3") (pin "49") (pinfunction "49_49") (pintype "passive"))
    )
    (net (code "140") (name "/B16_L3_P") (class "Default")
      (node (ref "*1") (pin "286") (pinfunction "B16_L3_P_C14_286") (pintype "passive"))
      (node (ref "*3") (pin "47") (pinfunction "47_47") (pintype "passive"))
    )
    (net (code "141") (name "/B16_L4_N") (class "Default")
      (node (ref "*1") (pin "65") (pinfunction "B16_L4_N_E14_65") (pintype "passive"))
      (node (ref "*3") (pin "28") (pinfunction "28_28") (pintype "passive"))
    )
    (net (code "142") (name "/B16_L4_P") (class "Default")
      (node (ref "*1") (pin "67") (pinfunction "B16_L4_P_E13_67") (pintype "passive"))
      (node (ref "*3") (pin "26") (pinfunction "26_26") (pintype "passive"))
    )
    (net (code "143") (name "/B16_L5_N") (class "Default")
      (node (ref "*1") (pin "283") (pinfunction "B16_L5_N_D16_283") (pintype "passive"))
      (node (ref "*3") (pin "46") (pinfunction "46_46") (pintype "passive"))
    )
    (net (code "144") (name "/B16_L5_P") (class "Default")
      (node (ref "*1") (pin "281") (pinfunction "B16_L5_P_E16_281") (pintype "passive"))
      (node (ref "*3") (pin "44") (pinfunction "44_44") (pintype "passive"))
    )
    (net (code "145") (name "/B16_L6_N") (class "Default")
      (node (ref "*1") (pin "71") (pinfunction "B16_L6_N_D15_71") (pintype "passive"))
      (node (ref "*3") (pin "22") (pinfunction "22_22") (pintype "passive"))
    )
    (net (code "146") (name "/B16_L6_P") (class "Default")
      (node (ref "*1") (pin "73") (pinfunction "B16_L6_P_D14_73") (pintype "passive"))
      (node (ref "*3") (pin "20") (pinfunction "20_20") (pintype "passive"))
    )
    (net (code "147") (name "/B16_L7_N") (class "Default")
      (node (ref "*1") (pin "287") (pinfunction "B16_L7_N_B16_287") (pintype "passive"))
      (node (ref "*3") (pin "50") (pinfunction "50_50") (pintype "passive"))
    )
    (net (code "148") (name "/B16_L7_P") (class "Default")
      (node (ref "*1") (pin "285") (pinfunction "B16_L7_P_B15_285") (pintype "passive"))
      (node (ref "*3") (pin "48") (pinfunction "48_48") (pintype "passive"))
    )
    (net (code "149") (name "/B16_L8_N") (class "Default")
      (node (ref "*1") (pin "77") (pinfunction "B16_L8_N_B13_77") (pintype "passive"))
      (node (ref "*3") (pin "16") (pinfunction "16_16") (pintype "passive"))
    )
    (net (code "150") (name "/B16_L8_P") (class "Default")
      (node (ref "*1") (pin "75") (pinfunction "B16_L8_P_C13_75") (pintype "passive"))
      (node (ref "*3") (pin "18") (pinfunction "18_18") (pintype "passive"))
    )
    (net (code "151") (name "/B16_L9_N") (class "Default")
      (node (ref "*1") (pin "293") (pinfunction "B16_L9_N_A16_293") (pintype "passive"))
      (node (ref "*3") (pin "56") (pinfunction "56_56") (pintype "passive"))
    )
    (net (code "152") (name "/B16_L9_P") (class "Default")
      (node (ref "*1") (pin "291") (pinfunction "B16_L9_P_A15_291") (pintype "passive"))
      (node (ref "*3") (pin "54") (pinfunction "54_54") (pintype "passive"))
    )
    (net (code "153") (name "/B16_L10_N") (class "Default")
      (node (ref "*1") (pin "294") (pinfunction "B16_L10_N_A14_294") (pintype "passive"))
      (node (ref "*3") (pin "55") (pinfunction "55_55") (pintype "passive"))
    )
    (net (code "154") (name "/B16_L10_P") (class "Default")
      (node (ref "*1") (pin "292") (pinfunction "B16_L10_P_A13_292") (pintype "passive"))
      (node (ref "*3") (pin "53") (pinfunction "53_53") (pintype "passive"))
    )
    (net (code "155") (name "/B16_L11_N") (class "Default")
      (node (ref "*1") (pin "297") (pinfunction "B16_L11_N_B18_297") (pintype "passive"))
      (node (ref "*3") (pin "60") (pinfunction "60_60") (pintype "passive"))
    )
    (net (code "156") (name "/B16_L11_P") (class "Default")
      (node (ref "*1") (pin "295") (pinfunction "B16_L11_P_B17_295") (pintype "passive"))
      (node (ref "*3") (pin "58") (pinfunction "58_58") (pintype "passive"))
    )
    (net (code "157") (name "/B16_L12_N") (class "Default")
      (node (ref "*1") (pin "298") (pinfunction "B16_L12_N_C17_298") (pintype "passive"))
      (node (ref "*3") (pin "59") (pinfunction "59_59") (pintype "passive"))
    )
    (net (code "158") (name "/B16_L12_P") (class "Default")
      (node (ref "*1") (pin "296") (pinfunction "B16_L12_P_D17_296") (pintype "passive"))
      (node (ref "*3") (pin "57") (pinfunction "57_57") (pintype "passive"))
    )
    (net (code "159") (name "/B16_L13_N") (class "Default")
      (node (ref "*1") (pin "303") (pinfunction "B16_L13_N_C19_303") (pintype "passive"))
      (node (ref "*3") (pin "66") (pinfunction "66_66") (pintype "passive"))
    )
    (net (code "160") (name "/B16_L13_P") (class "Default")
      (node (ref "*1") (pin "301") (pinfunction "B16_L13_P_C18_301") (pintype "passive"))
      (node (ref "*3") (pin "64") (pinfunction "64_64") (pintype "passive"))
    )
    (net (code "161") (name "/B16_L14_N") (class "Default")
      (node (ref "*1") (pin "304") (pinfunction "B16_L14_N_D19_304") (pintype "passive"))
      (node (ref "*3") (pin "65") (pinfunction "65_65") (pintype "passive"))
    )
    (net (code "162") (name "/B16_L14_P") (class "Default")
      (node (ref "*1") (pin "302") (pinfunction "B16_L14_P_E19_302") (pintype "passive"))
      (node (ref "*3") (pin "63") (pinfunction "63_63") (pintype "passive"))
    )
    (net (code "163") (name "/B16_L15_N") (class "Default")
      (node (ref "*1") (pin "307") (pinfunction "B16_L15_N_E18_307") (pintype "passive"))
      (node (ref "*3") (pin "70") (pinfunction "70_70") (pintype "passive"))
    )
    (net (code "164") (name "/B16_L15_P") (class "Default")
      (node (ref "*1") (pin "305") (pinfunction "B16_L15_P_F18_305") (pintype "passive"))
      (node (ref "*3") (pin "68") (pinfunction "68_68") (pintype "passive"))
    )
    (net (code "165") (name "/B16_L16_N") (class "Default")
      (node (ref "*1") (pin "308") (pinfunction "B16_L16_N_A20_308") (pintype "passive"))
      (node (ref "*3") (pin "69") (pinfunction "69_69") (pintype "passive"))
    )
    (net (code "166") (name "/B16_L16_P") (class "Default")
      (node (ref "*1") (pin "306") (pinfunction "B16_L16_P_B20_306") (pintype "passive"))
      (node (ref "*3") (pin "67") (pinfunction "67_67") (pintype "passive"))
    )
    (net (code "167") (name "/B16_L17_N") (class "Default")
      (node (ref "*1") (pin "313") (pinfunction "B16_L17_N_A19_313") (pintype "passive"))
      (node (ref "*3") (pin "76") (pinfunction "76_76") (pintype "passive"))
    )
    (net (code "168") (name "/B16_L17_P") (class "Default")
      (node (ref "*1") (pin "311") (pinfunction "B16_L17_P_A18_311") (pintype "passive"))
      (node (ref "*3") (pin "74") (pinfunction "74_74") (pintype "passive"))
    )
    (net (code "169") (name "/B16_L18_N") (class "Default")
      (node (ref "*1") (pin "314") (pinfunction "B16_L18_N_F20_314") (pintype "passive"))
      (node (ref "*3") (pin "75") (pinfunction "75_75") (pintype "passive"))
    )
    (net (code "170") (name "/B16_L18_P") (class "Default")
      (node (ref "*1") (pin "312") (pinfunction "B16_L18_P_F19_312") (pintype "passive"))
      (node (ref "*3") (pin "73") (pinfunction "73_73") (pintype "passive"))
    )
    (net (code "171") (name "/B16_L19_N") (class "Default")
      (node (ref "*1") (pin "317") (pinfunction "B16_L19_N_C20_317") (pintype "passive"))
      (node (ref "*3") (pin "80") (pinfunction "80_80") (pintype "passive"))
    )
    (net (code "172") (name "/B16_L19_P") (class "Default")
      (node (ref "*1") (pin "315") (pinfunction "B16_L19_P_D20_315") (pintype "passive"))
      (node (ref "*3") (pin "78") (pinfunction "78_78") (pintype "passive"))
    )
    (net (code "173") (name "/B16_L20_N") (class "Default")
      (node (ref "*1") (pin "318") (pinfunction "B16_L20_N_B22_318") (pintype "passive"))
      (node (ref "*3") (pin "79") (pinfunction "79_79") (pintype "passive"))
    )
    (net (code "174") (name "/B16_L20_P") (class "Default")
      (node (ref "*1") (pin "316") (pinfunction "B16_L20_P_C22_316") (pintype "passive"))
      (node (ref "*3") (pin "77") (pinfunction "77_77") (pintype "passive"))
    )
    (net (code "175") (name "/B16_L21_N") (class "Default")
      (node (ref "*1") (pin "166") (pinfunction "B16_L21_N_A21_166") (pintype "passive"))
      (node (ref "*4") (pin "5") (pinfunction "5_5") (pintype "passive"))
    )
    (net (code "176") (name "/B16_L21_P") (class "Default")
      (node (ref "*1") (pin "168") (pinfunction "B16_L21_P_B21_168") (pintype "passive"))
      (node (ref "*4") (pin "7") (pinfunction "7_7") (pintype "passive"))
    )
    (net (code "177") (name "/B16_L22_N") (class "Default")
      (node (ref "*1") (pin "178") (pinfunction "B16_L22_N_D22_178") (pintype "passive"))
      (node (ref "*4") (pin "17") (pinfunction "17_17") (pintype "passive"))
    )
    (net (code "178") (name "/B16_L22_P") (class "Default")
      (node (ref "*1") (pin "176") (pinfunction "B16_L22_P_E22_176") (pintype "passive"))
      (node (ref "*4") (pin "15") (pinfunction "15_15") (pintype "passive"))
    )
    (net (code "179") (name "/B16_L23_N") (class "Default")
      (node (ref "*1") (pin "174") (pinfunction "B16_L23_N_D21_174") (pintype "passive"))
      (node (ref "*4") (pin "13") (pinfunction "13_13") (pintype "passive"))
    )
    (net (code "180") (name "/B16_L23_P") (class "Default")
      (node (ref "*1") (pin "172") (pinfunction "B16_L23_P_E21_172") (pintype "passive"))
      (node (ref "*4") (pin "11") (pinfunction "11_11") (pintype "passive"))
    )
    (net (code "181") (name "/B16_L24_N") (class "Default")
      (node (ref "*1") (pin "184") (pinfunction "B16_L24_N_G22_184") (pintype "passive"))
      (node (ref "*4") (pin "23") (pinfunction "23_23") (pintype "passive"))
    )
    (net (code "182") (name "/B16_L24_P") (class "Default")
      (node (ref "*1") (pin "182") (pinfunction "B16_L24_P_G21_182") (pintype "passive"))
      (node (ref "*4") (pin "21") (pinfunction "21_21") (pintype "passive"))
    )
    (net (code "183") (name "/B34_L18_N") (class "Default")
      (node (ref "*1") (pin "41") (pinfunction "B34_L18_N_AA6_41") (pintype "passive"))
      (node (ref "*3") (pin "40") (pinfunction "40_40") (pintype "passive"))
    )
    (net (code "184") (name "/B34_L18_P") (class "Default")
      (node (ref "*1") (pin "43") (pinfunction "B34_L18_P_Y6_43") (pintype "passive"))
      (node (ref "*3") (pin "38") (pinfunction "38_38") (pintype "passive"))
    )
    (net (code "185") (name "/B34_L19_N") (class "Default")
      (node (ref "*1") (pin "47") (pinfunction "B34_L19_N_W7_47") (pintype "passive"))
      (node (ref "*3") (pin "34") (pinfunction "34_34") (pintype "passive"))
    )
    (net (code "186") (name "/B34_L19_P") (class "Default")
      (node (ref "*1") (pin "45") (pinfunction "B34_L19_P_V7_45") (pintype "passive"))
      (node (ref "*3") (pin "36") (pinfunction "36_36") (pintype "passive"))
    )
    (net (code "187") (name "/B34_L20_N") (class "Default")
      (node (ref "*1") (pin "38") (pinfunction "B34_L20_N_AB6_38") (pintype "passive"))
      (node (ref "*3") (pin "31") (pinfunction "31_31") (pintype "passive"))
    )
    (net (code "188") (name "/B34_L20_P") (class "Default")
      (node (ref "*1") (pin "36") (pinfunction "B34_L20_P_AB7_36") (pintype "passive"))
      (node (ref "*3") (pin "29") (pinfunction "29_29") (pintype "passive"))
    )
    (net (code "189") (name "/B34_L21_N") (class "Default")
      (node (ref "*1") (pin "42") (pinfunction "B34_L21_N_V8_42") (pintype "passive"))
      (node (ref "*3") (pin "33") (pinfunction "33_33") (pintype "passive"))
    )
    (net (code "190") (name "/B34_L21_P") (class "Default")
      (node (ref "*1") (pin "44") (pinfunction "B34_L21_P_V9_44") (pintype "passive"))
      (node (ref "*3") (pin "35") (pinfunction "35_35") (pintype "passive"))
    )
    (net (code "191") (name "/B34_L22_N") (class "Default")
      (node (ref "*1") (pin "48") (pinfunction "B34_L22_N_AB8_48") (pintype "passive"))
      (node (ref "*3") (pin "39") (pinfunction "39_39") (pintype "passive"))
    )
    (net (code "192") (name "/B34_L22_P") (class "Default")
      (node (ref "*1") (pin "46") (pinfunction "B34_L22_P_AA8_46") (pintype "passive"))
      (node (ref "*3") (pin "37") (pinfunction "37_37") (pintype "passive"))
    )
    (net (code "193") (name "/B34_L23_N") (class "Default")
      (node (ref "*1") (pin "37") (pinfunction "B34_L23_N_Y7_37") (pintype "passive"))
      (node (ref "*7") (pin "7") (pinfunction "7_7") (pintype "passive"))
    )
    (net (code "194") (name "/B34_L23_P") (class "Default")
      (node (ref "*1") (pin "35") (pinfunction "B34_L23_P_Y8_35") (pintype "passive"))
      (node (ref "*7") (pin "5") (pinfunction "5_5") (pintype "passive"))
    )
    (net (code "195") (name "/B34_L24_N") (class "Default")
      (node (ref "*1") (pin "58") (pinfunction "B34_L24_N_Y9_58") (pintype "passive"))
      (node (ref "*7") (pin "8") (pinfunction "8_8") (pintype "passive"))
    )
    (net (code "196") (name "/B34_L24_P") (class "Default")
      (node (ref "*1") (pin "56") (pinfunction "B34_L24_P_W9_56") (pintype "passive"))
      (node (ref "*7") (pin "6") (pinfunction "6_6") (pintype "passive"))
    )
    (net (code "197") (name "/B34_L25") (class "Default")
      (node (ref "*1") (pin "54") (pinfunction "B34_L25_U7_54") (pintype "passive"))
      (node (ref "*7") (pin "4") (pinfunction "4_4") (pintype "passive"))
    )
    (net (code "198") (name "/FPGA_TCK") (class "Default")
      (node (ref "*1") (pin "237") (pinfunction "FPGA_TCK_V12_237") (pintype "passive"))
      (node (ref "*6") (pin "38") (pinfunction "38_38") (pintype "passive"))
    )
    (net (code "199") (name "/FPGA_TDI") (class "Default")
      (node (ref "*1") (pin "238") (pinfunction "FPGA_TDI_R13_238") (pintype "passive"))
      (node (ref "*6") (pin "37") (pinfunction "37_37") (pintype "passive"))
    )
    (net (code "200") (name "/FPGA_TDO") (class "Default")
      (node (ref "*1") (pin "239") (pinfunction "FPGA_TDO_U13_239") (pintype "passive"))
      (node (ref "*6") (pin "40") (pinfunction "40_40") (pintype "passive"))
    )
    (net (code "201") (name "/FPGA_TMS") (class "Default")
      (node (ref "*1") (pin "240") (pinfunction "FPGA_TMS_T13_240") (pintype "passive"))
      (node (ref "*6") (pin "39") (pinfunction "39_39") (pintype "passive"))
    )
    (net (code "202") (name "/MGT_CLK_N") (class "Default")
      (node (ref "*1") (pin "278") (pinfunction "MGT_CLK1_N_E10_278") (pintype "passive"))
      (node (ref "*7") (pin "11") (pinfunction "11_11") (pintype "passive"))
    )
    (net (code "203") (name "/MGT_CLK_P") (class "Default")
      (node (ref "*1") (pin "276") (pinfunction "MGT_CLK1_P_F10_276") (pintype "passive"))
      (node (ref "*7") (pin "13") (pinfunction "13_13") (pintype "passive"))
    )
    (net (code "204") (name "/MGT_RX0_N") (class "Default")
      (node (ref "*1") (pin "272") (pinfunction "MGT_RX0_N_A8_272") (pintype "passive"))
      (node (ref "*7") (pin "17") (pinfunction "17_17") (pintype "passive"))
    )
    (net (code "205") (name "/MGT_RX0_P") (class "Default")
      (node (ref "*1") (pin "270") (pinfunction "MGT_RX0_P_B8_270") (pintype "passive"))
      (node (ref "*7") (pin "19") (pinfunction "19_19") (pintype "passive"))
    )
    (net (code "206") (name "/MGT_RX1_N") (class "Default")
      (node (ref "*1") (pin "277") (pinfunction "MGT_RX1_N_C11_277") (pintype "passive"))
      (node (ref "*7") (pin "18") (pinfunction "18_18") (pintype "passive"))
    )
    (net (code "207") (name "/MGT_RX1_P") (class "Default")
      (node (ref "*1") (pin "275") (pinfunction "MGT_RX1_P_D11_275") (pintype "passive"))
      (node (ref "*7") (pin "20") (pinfunction "20_20") (pintype "passive"))
    )
    (net (code "208") (name "/MGT_RX2_N") (class "Default")
      (node (ref "*1") (pin "260") (pinfunction "MGT_RX2_N_A10_260") (pintype "passive"))
      (node (ref "*7") (pin "29") (pinfunction "29_29") (pintype "passive"))
    )
    (net (code "209") (name "/MGT_RX2_P") (class "Default")
      (node (ref "*1") (pin "258") (pinfunction "MGT_RX2_P_B10_258") (pintype "passive"))
      (node (ref "*7") (pin "31") (pinfunction "31_31") (pintype "passive"))
    )
    (net (code "210") (name "/MGT_RX3_N") (class "Default")
      (node (ref "*1") (pin "265") (pinfunction "MGT_RX3_N_C9_265") (pintype "passive"))
      (node (ref "*7") (pin "30") (pinfunction "30_30") (pintype "passive"))
    )
    (net (code "211") (name "/MGT_RX3_P") (class "Default")
      (node (ref "*1") (pin "263") (pinfunction "MGT_RX3_P_D9_263") (pintype "passive"))
      (node (ref "*7") (pin "32") (pinfunction "32_32") (pintype "passive"))
    )
    (net (code "212") (name "/MGT_TX0_N") (class "Default")
      (node (ref "*1") (pin "266") (pinfunction "MGT_TX0_N_A4_266") (pintype "passive"))
      (node (ref "*7") (pin "23") (pinfunction "23_23") (pintype "passive"))
    )
    (net (code "213") (name "/MGT_TX0_P") (class "Default")
      (node (ref "*1") (pin "264") (pinfunction "MGT_TX0_P_B4_264") (pintype "passive"))
      (node (ref "*7") (pin "25") (pinfunction "25_25") (pintype "passive"))
    )
    (net (code "214") (name "/MGT_TX1_N") (class "Default")
      (node (ref "*1") (pin "271") (pinfunction "MGT_TX1_N_C5_271") (pintype "passive"))
      (node (ref "*7") (pin "24") (pinfunction "24_24") (pintype "passive"))
    )
    (net (code "215") (name "/MGT_TX1_P") (class "Default")
      (node (ref "*1") (pin "269") (pinfunction "MGT_TX1_P_D5_269") (pintype "passive"))
      (node (ref "*7") (pin "26") (pinfunction "26_26") (pintype "passive"))
    )
    (net (code "216") (name "/MGT_TX2_N") (class "Default")
      (node (ref "*1") (pin "254") (pinfunction "MGT_TX2_N_A6_254") (pintype "passive"))
      (node (ref "*7") (pin "35") (pinfunction "35_35") (pintype "passive"))
    )
    (net (code "217") (name "/MGT_TX2_P") (class "Default")
      (node (ref "*1") (pin "252") (pinfunction "MGT_TX2_P_B6_252") (pintype "passive"))
      (node (ref "*7") (pin "37") (pinfunction "37_37") (pintype "passive"))
    )
    (net (code "218") (name "/MGT_TX3_N") (class "Default")
      (node (ref "*1") (pin "259") (pinfunction "MGT_TX3_N_C7_259") (pintype "passive"))
      (node (ref "*7") (pin "36") (pinfunction "36_36") (pintype "passive"))
    )
    (net (code "219") (name "/MGT_TX3_P") (class "Default")
      (node (ref "*1") (pin "257") (pinfunction "MGT_TX3_P_D7_257") (pintype "passive"))
      (node (ref "*7") (pin "38") (pinfunction "38_38") (pintype "passive"))
    )
    (net (code "220") (name "/XADC_VN") (class "Default")
      (node (ref "*1") (pin "51") (pinfunction "XADC_VN_M9_51") (pintype "passive"))
      (node (ref "*7") (pin "12") (pinfunction "12_12") (pintype "passive"))
    )
    (net (code "221") (name "/XADC_VP") (class "Default")
      (node (ref "*1") (pin "53") (pinfunction "XADC_VP_L10_53") (pintype "passive"))
      (node (ref "*7") (pin "14") (pinfunction "14_14") (pintype "passive"))
    )
    (net (code "222") (name "GND") (class "Default")
      (node (ref "*1") (pin "10") (pinfunction "GND_10") (pintype "passive"))
      (node (ref "*1") (pin "100") (pinfunction "GND_100") (pintype "passive"))
      (node (ref "*1") (pin "109") (pinfunction "GND_109") (pintype "passive"))
      (node (ref "*1") (pin "110") (pinfunction "GND_110") (pintype "passive"))
      (node (ref "*1") (pin "119") (pinfunction "GND_119") (pintype "passive"))
      (node (ref "*1") (pin "120") (pinfunction "GND_120") (pintype "passive"))
      (node (ref "*1") (pin "129") (pinfunction "GND_129") (pintype "passive"))
      (node (ref "*1") (pin "130") (pinfunction "GND_130") (pintype "passive"))
      (node (ref "*1") (pin "139") (pinfunction "GND_139") (pintype "passive"))
      (node (ref "*1") (pin "140") (pinfunction "GND_140") (pintype "passive"))
      (node (ref "*1") (pin "149") (pinfunction "GND_149") (pintype "passive"))
      (node (ref "*1") (pin "150") (pinfunction "GND_150") (pintype "passive"))
      (node (ref "*1") (pin "169") (pinfunction "GND_169") (pintype "passive"))
      (node (ref "*1") (pin "170") (pinfunction "GND_170") (pintype "passive"))
      (node (ref "*1") (pin "179") (pinfunction "GND_179") (pintype "passive"))
      (node (ref "*1") (pin "180") (pinfunction "GND_180") (pintype "passive"))
      (node (ref "*1") (pin "189") (pinfunction "GND_189") (pintype "passive"))
      (node (ref "*1") (pin "19") (pinfunction "GND_19") (pintype "passive"))
      (node (ref "*1") (pin "190") (pinfunction "GND_190") (pintype "passive"))
      (node (ref "*1") (pin "199") (pinfunction "GND_199") (pintype "passive"))
      (node (ref "*1") (pin "20") (pinfunction "GND_20") (pintype "passive"))
      (node (ref "*1") (pin "200") (pinfunction "GND_200") (pintype "passive"))
      (node (ref "*1") (pin "209") (pinfunction "GND_209") (pintype "passive"))
      (node (ref "*1") (pin "210") (pinfunction "GND_210") (pintype "passive"))
      (node (ref "*1") (pin "219") (pinfunction "GND_219") (pintype "passive"))
      (node (ref "*1") (pin "220") (pinfunction "GND_220") (pintype "passive"))
      (node (ref "*1") (pin "229") (pinfunction "GND_229") (pintype "passive"))
      (node (ref "*1") (pin "230") (pinfunction "GND_230") (pintype "passive"))
      (node (ref "*1") (pin "249") (pinfunction "GND_249") (pintype "passive"))
      (node (ref "*1") (pin "250") (pinfunction "GND_250") (pintype "passive"))
      (node (ref "*1") (pin "255") (pinfunction "GND_255") (pintype "passive"))
      (node (ref "*1") (pin "256") (pinfunction "GND_256") (pintype "passive"))
      (node (ref "*1") (pin "261") (pinfunction "GND_261") (pintype "passive"))
      (node (ref "*1") (pin "262") (pinfunction "GND_262") (pintype "passive"))
      (node (ref "*1") (pin "267") (pinfunction "GND_267") (pintype "passive"))
      (node (ref "*1") (pin "268") (pinfunction "GND_268") (pintype "passive"))
      (node (ref "*1") (pin "273") (pinfunction "GND_273") (pintype "passive"))
      (node (ref "*1") (pin "274") (pinfunction "GND_274") (pintype "passive"))
      (node (ref "*1") (pin "279") (pinfunction "GND_279") (pintype "passive"))
      (node (ref "*1") (pin "280") (pinfunction "GND_280") (pintype "passive"))
      (node (ref "*1") (pin "289") (pinfunction "GND_289") (pintype "passive"))
      (node (ref "*1") (pin "29") (pinfunction "GND_29") (pintype "passive"))
      (node (ref "*1") (pin "290") (pinfunction "GND_290") (pintype "passive"))
      (node (ref "*1") (pin "299") (pinfunction "GND_299") (pintype "passive"))
      (node (ref "*1") (pin "30") (pinfunction "GND_30") (pintype "passive"))
      (node (ref "*1") (pin "300") (pinfunction "GND_300") (pintype "passive"))
      (node (ref "*1") (pin "309") (pinfunction "GND_309") (pintype "passive"))
      (node (ref "*1") (pin "310") (pinfunction "GND_310") (pintype "passive"))
      (node (ref "*1") (pin "39") (pinfunction "GND_39") (pintype "passive"))
      (node (ref "*1") (pin "40") (pinfunction "GND_40") (pintype "passive"))
      (node (ref "*1") (pin "49") (pinfunction "GND_49") (pintype "passive"))
      (node (ref "*1") (pin "50") (pinfunction "GND_50") (pintype "passive"))
      (node (ref "*1") (pin "59") (pinfunction "GND_59") (pintype "passive"))
      (node (ref "*1") (pin "60") (pinfunction "GND_60") (pintype "passive"))
      (node (ref "*1") (pin "69") (pinfunction "GND_69") (pintype "passive"))
      (node (ref "*1") (pin "70") (pinfunction "GND_70") (pintype "passive"))
      (node (ref "*1") (pin "89") (pinfunction "GND_89") (pintype "passive"))
      (node (ref "*1") (pin "9") (pinfunction "GND_9") (pintype "passive"))
      (node (ref "*1") (pin "90") (pinfunction "GND_90") (pintype "passive"))
      (node (ref "*1") (pin "99") (pinfunction "GND_99") (pintype "passive"))
      (node (ref "*2") (pin "10") (pinfunction "10_10") (pintype "passive"))
      (node (ref "*2") (pin "11") (pinfunction "11_11") (pintype "passive"))
      (node (ref "*2") (pin "12") (pinfunction "12_12") (pintype "passive"))
      (node (ref "*2") (pin "21") (pinfunction "21_21") (pintype "passive"))
      (node (ref "*2") (pin "22") (pinfunction "22_22") (pintype "passive"))
      (node (ref "*2") (pin "31") (pinfunction "31_31") (pintype "passive"))
      (node (ref "*2") (pin "32") (pinfunction "32_32") (pintype "passive"))
      (node (ref "*2") (pin "9") (pinfunction "9_9") (pintype "passive"))
      (node (ref "*3") (pin "13") (pinfunction "13_13") (pintype "passive"))
      (node (ref "*3") (pin "14") (pinfunction "14_14") (pintype "passive"))
      (node (ref "*3") (pin "23") (pinfunction "23_23") (pintype "passive"))
      (node (ref "*3") (pin "24") (pinfunction "24_24") (pintype "passive"))
      (node (ref "*3") (pin "41") (pinfunction "41_41") (pintype "passive"))
      (node (ref "*3") (pin "42") (pinfunction "42_42") (pintype "passive"))
      (node (ref "*3") (pin "51") (pinfunction "51_51") (pintype "passive"))
      (node (ref "*3") (pin "52") (pinfunction "52_52") (pintype "passive"))
      (node (ref "*3") (pin "61") (pinfunction "61_61") (pintype "passive"))
      (node (ref "*3") (pin "62") (pinfunction "62_62") (pintype "passive"))
      (node (ref "*3") (pin "7") (pinfunction "7_7") (pintype "passive"))
      (node (ref "*3") (pin "71") (pinfunction "71_71") (pintype "passive"))
      (node (ref "*3") (pin "72") (pinfunction "72_72") (pintype "passive"))
      (node (ref "*3") (pin "8") (pinfunction "8_8") (pintype "passive"))
      (node (ref "*4") (pin "10") (pinfunction "10_10") (pintype "passive"))
      (node (ref "*4") (pin "19") (pinfunction "19_19") (pintype "passive"))
      (node (ref "*4") (pin "20") (pinfunction "20_20") (pintype "passive"))
      (node (ref "*4") (pin "29") (pinfunction "29_29") (pintype "passive"))
      (node (ref "*4") (pin "30") (pinfunction "30_30") (pintype "passive"))
      (node (ref "*4") (pin "39") (pinfunction "39_39") (pintype "passive"))
      (node (ref "*4") (pin "40") (pinfunction "40_40") (pintype "passive"))
      (node (ref "*4") (pin "9") (pinfunction "9_9") (pintype "passive"))
      (node (ref "*5") (pin "10") (pinfunction "10_10") (pintype "passive"))
      (node (ref "*5") (pin "19") (pinfunction "19_19") (pintype "passive"))
      (node (ref "*5") (pin "20") (pinfunction "20_20") (pintype "passive"))
      (node (ref "*5") (pin "29") (pinfunction "29_29") (pintype "passive"))
      (node (ref "*5") (pin "30") (pinfunction "30_30") (pintype "passive"))
      (node (ref "*5") (pin "39") (pinfunction "39_39") (pintype "passive"))
      (node (ref "*5") (pin "40") (pinfunction "40_40") (pintype "passive"))
      (node (ref "*5") (pin "49") (pinfunction "49_49") (pintype "passive"))
      (node (ref "*5") (pin "50") (pinfunction "50_50") (pintype "passive"))
      (node (ref "*5") (pin "59") (pinfunction "59_59") (pintype "passive"))
      (node (ref "*5") (pin "60") (pinfunction "60_60") (pintype "passive"))
      (node (ref "*5") (pin "69") (pinfunction "69_69") (pintype "passive"))
      (node (ref "*5") (pin "70") (pinfunction "70_70") (pintype "passive"))
      (node (ref "*5") (pin "9") (pinfunction "9_9") (pintype "passive"))
      (node (ref "*6") (pin "10") (pinfunction "10_10") (pintype "passive"))
      (node (ref "*6") (pin "19") (pinfunction "19_19") (pintype "passive"))
      (node (ref "*6") (pin "20") (pinfunction "20_20") (pintype "passive"))
      (node (ref "*6") (pin "29") (pinfunction "29_29") (pintype "passive"))
      (node (ref "*6") (pin "30") (pinfunction "30_30") (pintype "passive"))
      (node (ref "*6") (pin "35") (pinfunction "35_35") (pintype "passive"))
      (node (ref "*6") (pin "36") (pinfunction "36_36") (pintype "passive"))
      (node (ref "*6") (pin "9") (pinfunction "9_9") (pintype "passive"))
      (node (ref "*7") (pin "10") (pinfunction "10_10") (pintype "passive"))
      (node (ref "*7") (pin "15") (pinfunction "15_15") (pintype "passive"))
      (node (ref "*7") (pin "16") (pinfunction "16_16") (pintype "passive"))
      (node (ref "*7") (pin "21") (pinfunction "21_21") (pintype "passive"))
      (node (ref "*7") (pin "22") (pinfunction "22_22") (pintype "passive"))
      (node (ref "*7") (pin "27") (pinfunction "27_27") (pintype "passive"))
      (node (ref "*7") (pin "28") (pinfunction "28_28") (pintype "passive"))
      (node (ref "*7") (pin "33") (pinfunction "33_33") (pintype "passive"))
      (node (ref "*7") (pin "34") (pinfunction "34_34") (pintype "passive"))
      (node (ref "*7") (pin "39") (pinfunction "39_39") (pintype "passive"))
      (node (ref "*7") (pin "40") (pinfunction "40_40") (pintype "passive"))
      (node (ref "*7") (pin "9") (pinfunction "9_9") (pintype "passive"))
    )
    (net (code "223") (name "fpga5V") (class "Default")
      (node (ref "*1") (pin "1") (pinfunction "VCCIN_1") (pintype "passive"))
      (node (ref "*1") (pin "2") (pinfunction "VCCIN_2") (pintype "passive"))
      (node (ref "*1") (pin "3") (pinfunction "VCCIN_3") (pintype "passive"))
      (node (ref "*1") (pin "4") (pinfunction "VCCIN_4") (pintype "passive"))
      (node (ref "*1") (pin "5") (pinfunction "VCCIN_5") (pintype "passive"))
      (node (ref "*1") (pin "6") (pinfunction "VCCIN_6") (pintype "passive"))
      (node (ref "*1") (pin "7") (pinfunction "VCCIN_7") (pintype "passive"))
      (node (ref "*1") (pin "8") (pinfunction "VCCIN_8") (pintype "passive"))
      (node (ref "*2") (pin "23") (pinfunction "23_23") (pintype "passive"))
      (node (ref "*2") (pin "24") (pinfunction "24_24") (pintype "passive"))
      (node (ref "*2") (pin "25") (pinfunction "25_25") (pintype "passive"))
      (node (ref "*2") (pin "26") (pinfunction "26_26") (pintype "passive"))
      (node (ref "*2") (pin "27") (pinfunction "27_27") (pintype "passive"))
      (node (ref "*2") (pin "28") (pinfunction "28_28") (pintype "passive"))
      (node (ref "*2") (pin "29") (pinfunction "29_29") (pintype "passive"))
      (node (ref "*2") (pin "30") (pinfunction "30_30") (pintype "passive"))
    )
    (net (code "224") (name "unconnected-(*1A-NC-Pad11)") (class "Default")
      (node (ref "*1") (pin "11") (pinfunction "NC_11") (pintype "passive"))
    )
    (net (code "225") (name "unconnected-(*1A-NC-Pad12)") (class "Default")
      (node (ref "*1") (pin "12") (pinfunction "NC_12") (pintype "passive"))
    )
    (net (code "226") (name "unconnected-(*1A-NC-Pad13)") (class "Default")
      (node (ref "*1") (pin "13") (pinfunction "NC_13") (pintype "passive"))
    )
    (net (code "227") (name "unconnected-(*1A-NC-Pad14)") (class "Default")
      (node (ref "*1") (pin "14") (pinfunction "NC_14") (pintype "passive"))
    )
    (net (code "228") (name "unconnected-(*1A-NC-Pad15)") (class "Default")
      (node (ref "*1") (pin "15") (pinfunction "NC_15") (pintype "passive"))
    )
    (net (code "229") (name "unconnected-(*1A-NC-Pad17)") (class "Default")
      (node (ref "*1") (pin "17") (pinfunction "NC_17") (pintype "passive"))
    )
    (net (code "230") (name "unconnected-(*1A-NC-Pad52)") (class "Default")
      (node (ref "*1") (pin "52") (pinfunction "NC_52") (pintype "passive"))
    )
    (net (code "231") (name "unconnected-(*1A-NC-Pad55)") (class "Default")
      (node (ref "*1") (pin "55") (pinfunction "NC_55") (pintype "passive"))
    )
    (net (code "232") (name "unconnected-(*1A-NC-Pad57)") (class "Default")
      (node (ref "*1") (pin "57") (pinfunction "NC_57") (pintype "passive"))
    )
    (net (code "233") (name "unconnected-(*1A-NC-Pad62)") (class "Default")
      (node (ref "*1") (pin "62") (pinfunction "NC_62") (pintype "passive"))
    )
    (net (code "234") (name "unconnected-(*1A-NC-Pad64)") (class "Default")
      (node (ref "*1") (pin "64") (pinfunction "NC_64") (pintype "passive"))
    )
    (net (code "235") (name "unconnected-(*1A-NC-Pad66)") (class "Default")
      (node (ref "*1") (pin "66") (pinfunction "NC_66") (pintype "passive"))
    )
    (net (code "236") (name "unconnected-(*1A-NC-Pad68)") (class "Default")
      (node (ref "*1") (pin "68") (pinfunction "NC_68") (pintype "passive"))
    )
    (net (code "237") (name "unconnected-(*1A-NC-Pad72)") (class "Default")
      (node (ref "*1") (pin "72") (pinfunction "NC_72") (pintype "passive"))
    )
    (net (code "238") (name "unconnected-(*1A-NC-Pad74)") (class "Default")
      (node (ref "*1") (pin "74") (pinfunction "NC_74") (pintype "passive"))
    )
    (net (code "239") (name "unconnected-(*1A-NC-Pad76)") (class "Default")
      (node (ref "*1") (pin "76") (pinfunction "NC_76") (pintype "passive"))
    )
    (net (code "240") (name "unconnected-(*1A-NC-Pad78)") (class "Default")
      (node (ref "*1") (pin "78") (pinfunction "NC_78") (pintype "passive"))
    )
    (net (code "241") (name "unconnected-(*1A-NC-Pad79)") (class "Default")
      (node (ref "*1") (pin "79") (pinfunction "NC_79") (pintype "passive"))
    )
    (net (code "242") (name "unconnected-(*1A-NC-Pad80)") (class "Default")
      (node (ref "*1") (pin "80") (pinfunction "NC_80") (pintype "passive"))
    )
    (net (code "243") (name "unconnected-(*1C-NC-Pad235)") (class "Default")
      (node (ref "*1") (pin "235") (pinfunction "NC_235") (pintype "passive"))
    )
    (net (code "244") (name "unconnected-(*1C-NC-Pad236)") (class "Default")
      (node (ref "*1") (pin "236") (pinfunction "NC_236") (pintype "passive"))
    )
    (net (code "245") (name "unconnected-(*1D-NC-Pad241)") (class "Default")
      (node (ref "*1") (pin "241") (pinfunction "NC_241") (pintype "passive"))
    )
    (net (code "246") (name "unconnected-(*1D-NC-Pad242)") (class "Default")
      (node (ref "*1") (pin "242") (pinfunction "NC_242") (pintype "passive"))
    )
    (net (code "247") (name "unconnected-(*1D-NC-Pad243)") (class "Default")
      (node (ref "*1") (pin "243") (pinfunction "NC_243") (pintype "passive"))
    )
    (net (code "248") (name "unconnected-(*1D-NC-Pad244)") (class "Default")
      (node (ref "*1") (pin "244") (pinfunction "NC_244") (pintype "passive"))
    )
    (net (code "249") (name "unconnected-(*1D-NC-Pad245)") (class "Default")
      (node (ref "*1") (pin "245") (pinfunction "NC_245") (pintype "passive"))
    )
    (net (code "250") (name "unconnected-(*1D-NC-Pad246)") (class "Default")
      (node (ref "*1") (pin "246") (pinfunction "NC_246") (pintype "passive"))
    )
    (net (code "251") (name "unconnected-(*1D-NC-Pad247)") (class "Default")
      (node (ref "*1") (pin "247") (pinfunction "NC_247") (pintype "passive"))
    )
    (net (code "252") (name "unconnected-(*1D-NC-Pad248)") (class "Default")
      (node (ref "*1") (pin "248") (pinfunction "NC_248") (pintype "passive"))
    )
    (net (code "253") (name "unconnected-(*1D-NC-Pad251)") (class "Default")
      (node (ref "*1") (pin "251") (pinfunction "NC_251") (pintype "passive"))
    )
    (net (code "254") (name "unconnected-(*1D-NC-Pad253)") (class "Default")
      (node (ref "*1") (pin "253") (pinfunction "NC_253") (pintype "passive"))
    )
    (net (code "255") (name "unconnected-(*1D-NC-Pad319)") (class "Default")
      (node (ref "*1") (pin "319") (pinfunction "NC_319") (pintype "passive"))
    )
    (net (code "256") (name "unconnected-(*1D-NC-Pad320)") (class "Default")
      (node (ref "*1") (pin "320") (pinfunction "NC_320") (pintype "passive"))
    )
    (net (code "257") (name "unconnected-(*2-Pad38)") (class "Default")
      (node (ref "*2") (pin "38") (pinfunction "38_38") (pintype "passive"))
    )
    (net (code "258") (name "unconnected-(*2-Pad40)") (class "Default")
      (node (ref "*2") (pin "40") (pinfunction "40_40") (pintype "passive"))
    )
    (net (code "259") (name "unconnected-(*7-Pad2)") (class "Default")
      (node (ref "*7") (pin "2") (pinfunction "2_2") (pintype "passive"))
    )
    (net (code "260") (name "unconnected-(SP1-Pad1)") (class "Default")
      (node (ref "SP1") (pin "1") (pinfunction "1_1") (pintype "passive"))
    )
    (net (code "261") (name "unconnected-(SP2-Pad1)") (class "Default")
      (node (ref "SP2") (pin "1") (pinfunction "1_1") (pintype "passive"))
    )
    (net (code "262") (name "unconnected-(SP3-Pad1)") (class "Default")
      (node (ref "SP3") (pin "1") (pinfunction "1_1") (pintype "passive"))
    )
    (net (code "263") (name "unconnected-(SP4-Pad1)") (class "Default")
      (node (ref "SP4") (pin "1") (pinfunction "1_1") (pintype "passive"))
    )
  )
)
